# Supply_12V_to_5V-7805_smd.net
KiCad netlist of a schematic drawn in Altium Designer
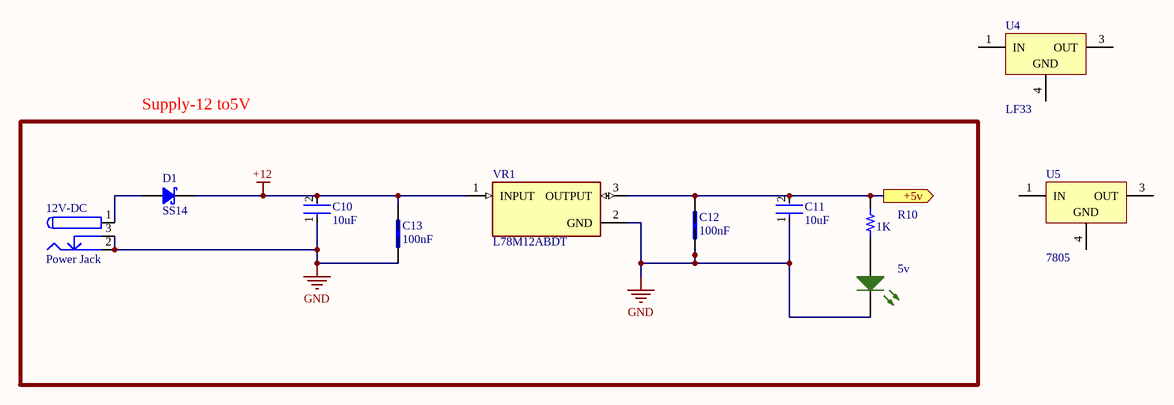
[diagram p0: Supply 12V to 5V-7805 smd.SchDoc]

(export (version "E")
  (design (tool "Eeschema 10.0.6"))
  (components
    (comp (ref "5v")
      (value "LED SMD 0805 GREEN")
      (footprint "LED_0805_GREEN")
      (libsource (lib "Led") (part "LED SMD 0805 GREEN"))
    )
    (comp (ref "12V-DC")
      (value "Power Jack")
      (footprint "DC005")
      (fields (field (name "PARTNUMBER") "DC005-5.5MM"))
      (libsource (lib "Conn Jack") (part "Power Jack"))
    )
    (comp (ref "C10")
      (value "10uF")
      (footprint "FP-C0805C-DN-IPC_B")
      (description "CAP CER 0.22UF 50V X7R 0805")
      (fields
        (field (name "MANUFACTURER") "KEMET")
        (field (name "OCTOPART") "https://octopart.com/c0805c224k5ractu-kemet-144670")
      )
      (libsource (lib "Altium Content Vault") (part "b4654b650e69147ec39a6b967a45e02"))
    )
    (comp (ref "C11")
      (value "10uF")
      (footprint "FP-C0805C-DN-IPC_A")
      (description "CAP CER 0.22UF 50V X7R 0805")
      (fields
        (field (name "MANUFACTURER") "KEMET")
        (field (name "OCTOPART") "https://octopart.com/c0805c224k5ractu-kemet-144670")
      )
      (libsource (lib "Altium Content Vault") (part "b4654b650e69147ec39a6b967a45e02"))
    )
    (comp (ref "C12")
      (value "100nF")
      (footprint "CAP 0805_2012")
      (description "COMMERCIAL CHIP STD JAPAN BULK - FN TAPE/REEL, 7 INCH PAPER TAPE-0805")
      (fields (field (name "MP") "LD051C182KAB2A"))
      (libsource (lib "cap 0805") (part "LD051C182KAB2A"))
    )
    (comp (ref "C13")
      (value "100nF")
      (footprint "CAP 0805_2012")
      (description "COMMERCIAL CHIP STD JAPAN BULK - FN TAPE/REEL, 7 INCH PAPER TAPE-0805")
      (fields (field (name "MP") "LD051C182KAB2A"))
      (libsource (lib "cap 0805") (part "LD051C182KAB2A"))
    )
    (comp (ref "D1")
      (value "SS14")
      (footprint "DO-214AC SMA")
      (description "Diode Schottky 40V 1A Surface Mount SMA (DO-214AC)")
      (libsource (lib "Diode") (part "SS14 (SMD SMA)"))
    )
    (comp (ref "R10")
      (value "1K")
      (footprint "RES 0805_2012")
      (description "SMT Resistor")
      (libsource (lib "Resistor") (part "Res 0805"))
    )
    (comp (ref "U4")
      (value "LF33")
      (footprint "TO-252")
      (description "500mA, Very Low Drop (0.45V) Voltage Regulator, 3.3V, 3-Pin DPAK, Tape and Reel")
      (fields (field (name "PARTNUMBER") "LF33CDT-TR"))
      (libsource (lib "Chip") (part "LF33 (SMD)"))
    )
    (comp (ref "U5")
      (value "7805")
      (footprint "TO-252")
      (description "Linear Voltage Regulator IC 1 Output 500mA TO-252-3")
      (fields
        (field (name "PARTNUMBER") "LM78M05CDTX/NOPB")
        (field (name "MANUFACTURER") "National Semiconductor")
      )
      (libsource (lib "Chip") (part "LM78M05 (SMD)"))
    )
    (comp (ref "VR1")
      (value "L78M12ABDT")
      (footprint "VREG_L78M12ABDT")
      (description "Linear Voltage Regulator IC Positive Fixed 1 Output 500mA DPAK")
      (fields (field (name "MF") "STMicroelectronics"))
      (libsource (lib "L78M12ABDT") (part "L78M12ABDT"))
    )
  )
  (nets
    (net (code "1") (name "+12") (class "Default")
      (node (ref "C10") (pin "2") (pinfunction "2_2") (pintype "passive"))
      (node (ref "C13") (pin "2") (pinfunction "2_2") (pintype "passive"))
      (node (ref "D1") (pin "2") (pinfunction "2_2") (pintype "passive"))
      (node (ref "VR1") (pin "1") (pinfunction "INPUT_1") (pintype "input"))
    )
    (net (code "2") (name "/+5v") (class "Default")
      (node (ref "C11") (pin "2") (pinfunction "2_2") (pintype "passive"))
      (node (ref "C12") (pin "2") (pinfunction "2_2") (pintype "passive"))
      (node (ref "R10") (pin "1") (pinfunction "1_1") (pintype "passive"))
      (node (ref "VR1") (pin "3") (pinfunction "OUTPUT_3") (pintype "bidirectional"))
    )
    (net (code "3") (name "GND") (class "Default")
      (node (ref "12V-DC") (pin "2") (pinfunction "2_2") (pintype "power_in"))
      (node (ref "12V-DC") (pin "3") (pinfunction "3_3") (pintype "power_in"))
      (node (ref "5v") (pin "2") (pinfunction "K_2") (pintype "passive"))
      (node (ref "C10") (pin "1") (pinfunction "1_1") (pintype "passive"))
      (node (ref "C11") (pin "1") (pinfunction "1_1") (pintype "passive"))
      (node (ref "C12") (pin "1") (pinfunction "1_1") (pintype "passive"))
      (node (ref "C13") (pin "1") (pinfunction "1_1") (pintype "passive"))
      (node (ref "VR1") (pin "2") (pinfunction "GND_2") (pintype "power_in"))
    )
    (net (code "4") (name "Net-(5v-A)") (class "Default")
      (node (ref "5v") (pin "1") (pinfunction "A_1") (pintype "passive"))
      (node (ref "R10") (pin "2") (pinfunction "2_2") (pintype "passive"))
    )
    (net (code "5") (name "Net-(12V-DC-Pad1)") (class "Default")
      (node (ref "12V-DC") (pin "1") (pinfunction "1_1") (pintype "power_in"))
      (node (ref "D1") (pin "1") (pinfunction "1_1") (pintype "passive"))
    )
    (net (code "6") (name "unconnected-(U4-GND-Pad4)") (class "Default")
      (node (ref "U4") (pin "4") (pinfunction "GND_4") (pintype "power_in"))
    )
    (net (code "7") (name "unconnected-(U4-IN-Pad1)") (class "Default")
      (node (ref "U4") (pin "1") (pinfunction "IN_1") (pintype "power_in"))
    )
    (net (code "8") (name "unconnected-(U4-OUT-Pad3)") (class "Default")
      (node (ref "U4") (pin "3") (pinfunction "OUT_3") (pintype "power_in"))
    )
    (net (code "9") (name "unconnected-(U5-GND-Pad4)") (class "Default")
      (node (ref "U5") (pin "4") (pinfunction "GND_4") (pintype "power_in"))
    )
    (net (code "10") (name "unconnected-(U5-IN-Pad1)") (class "Default")
      (node (ref "U5") (pin "1") (pinfunction "IN_1") (pintype "power_in"))
    )
    (net (code "11") (name "unconnected-(U5-OUT-Pad3)") (class "Default")
      (node (ref "U5") (pin "3") (pinfunction "OUT_3") (pintype "power_in"))
    )
  )
)
